# design.net
KiCad netlist of a schematic drawn in Altium Designer
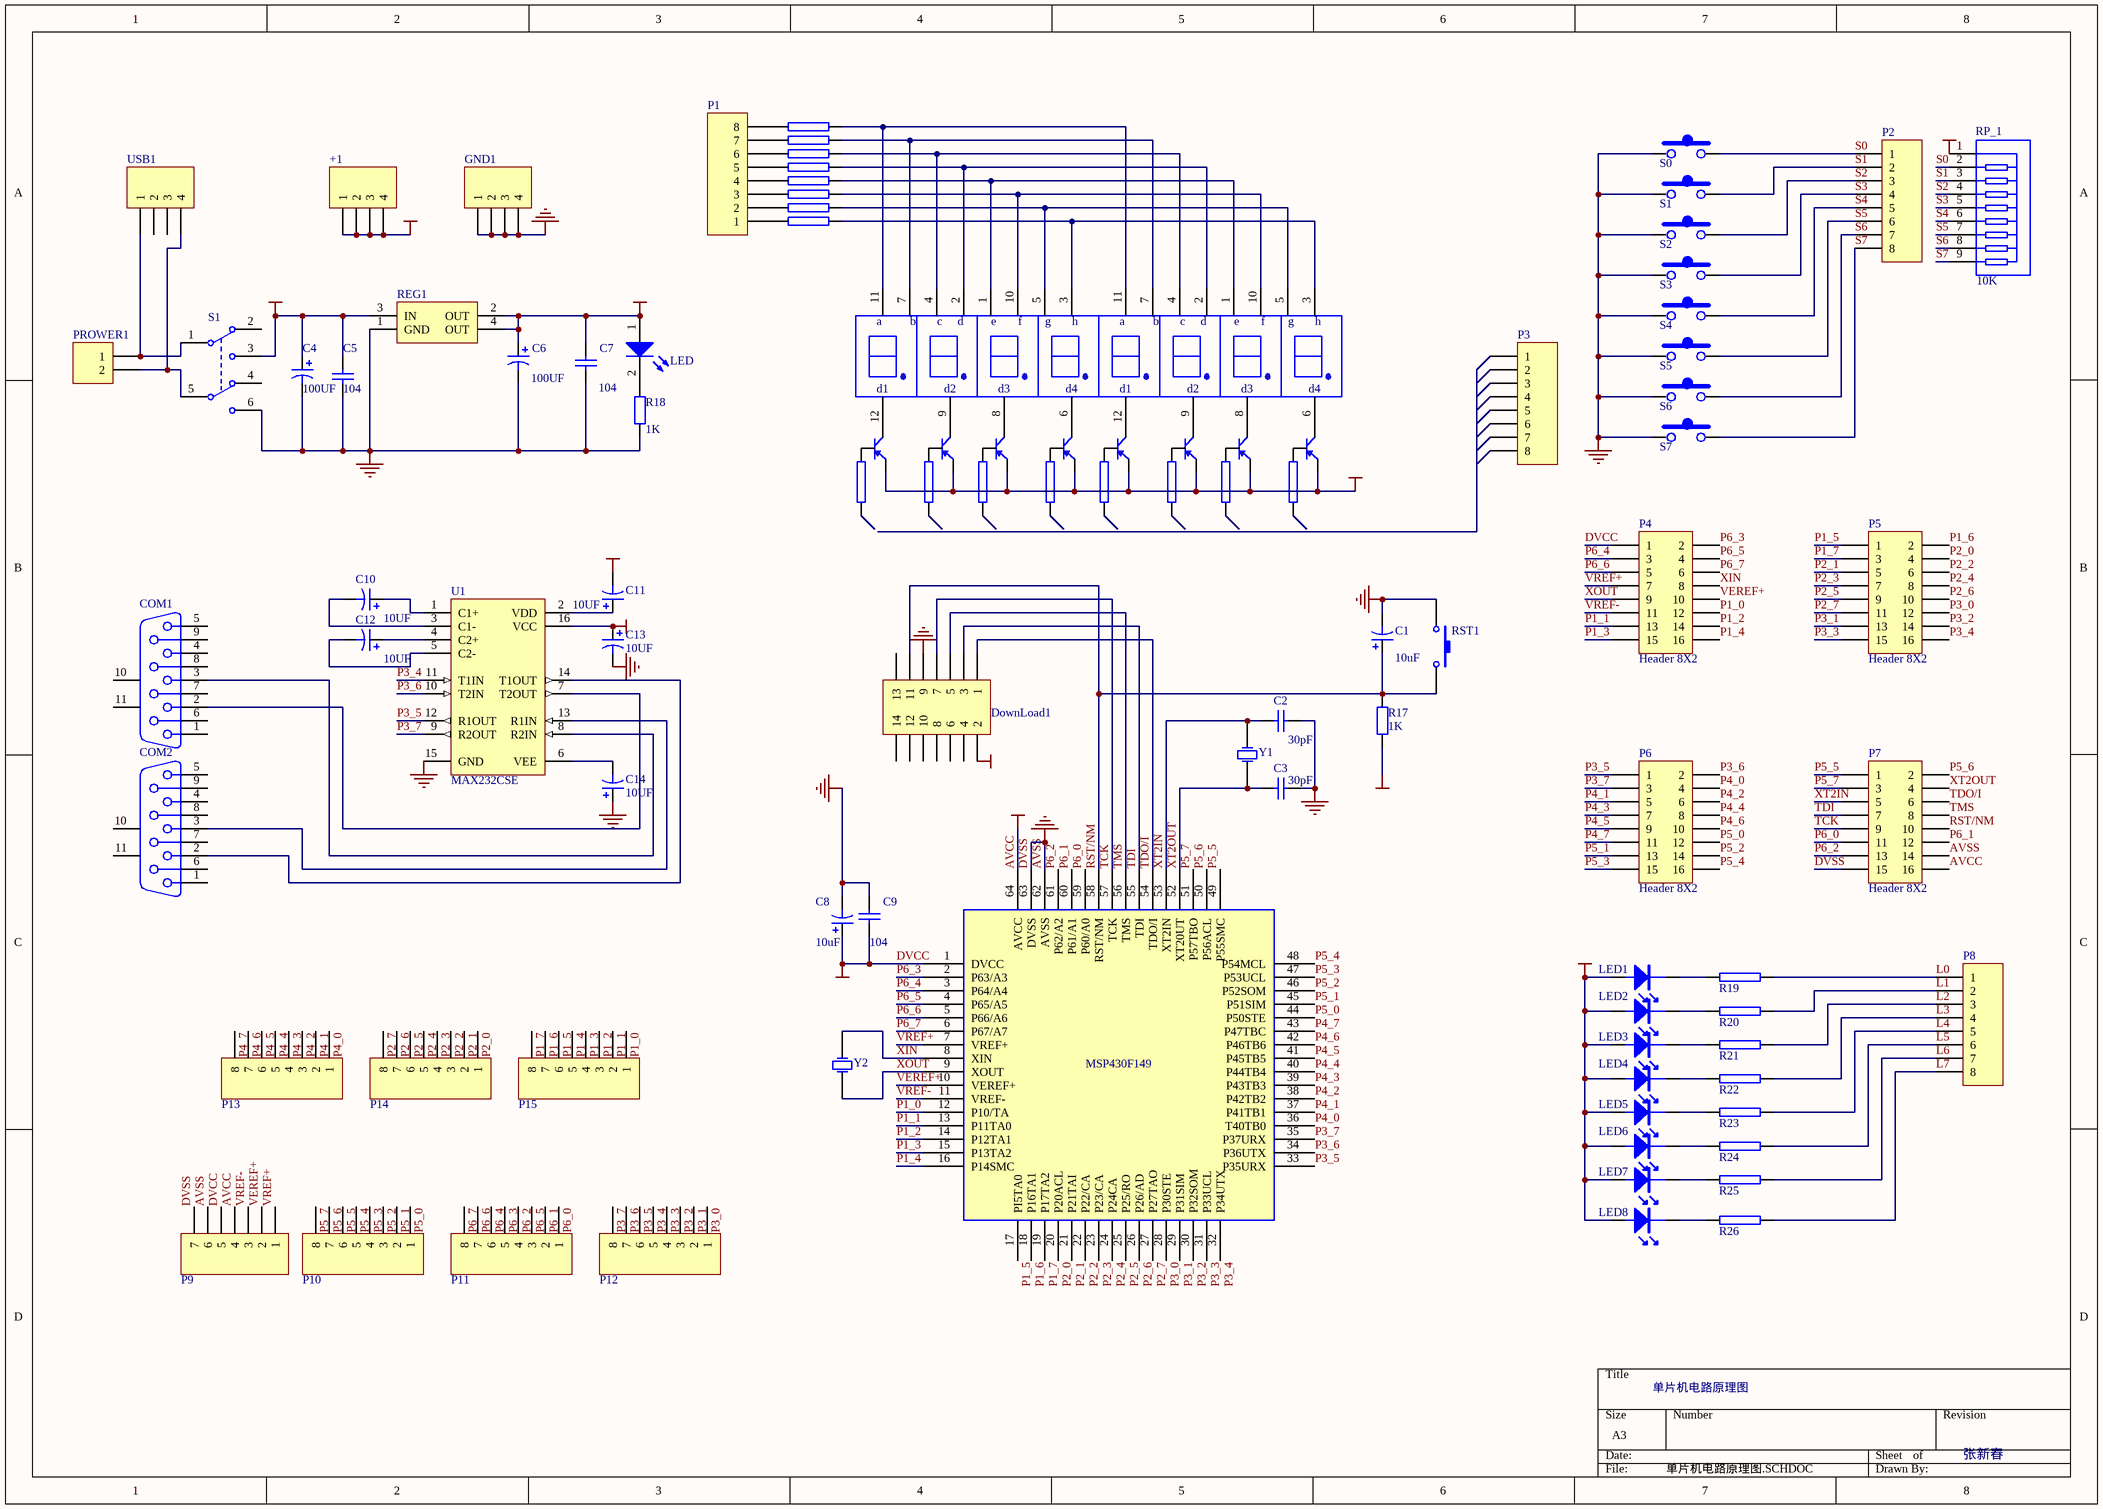
[diagram p0: 单片机电路原理图.SCHDOC]

(export (version "E")
  (design (tool "Eeschema 10.0.6"))
  (components
    (comp (ref "+1")
      (value "Header 4")
      (footprint "HDR1X4")
      (description "Header, 4-Pin")
      (fields (field (name "PUBLISHER") "Altium Limited"))
      (libsource (lib "Miscellaneous Connectors") (part "Header 4"))
    )
    (comp (ref "1") (value "S0") (footprint "an-6*6") (libsource (lib "OldCow1 (1)") (part "KEY")))
    (comp (ref "2") (value "S1") (footprint "an-6*6") (libsource (lib "OldCow1 (1)") (part "KEY")))
    (comp (ref "3") (value "S2") (footprint "an-6*6") (libsource (lib "OldCow1 (1)") (part "KEY")))
    (comp (ref "4") (value "LED8") (footprint "LED8PF") (libsource (lib "OldCow1 (1)") (part "LED8")))
    (comp (ref "5") (value "LED8") (footprint "LED8PF") (libsource (lib "OldCow1 (1)") (part "LED8")))
    (comp (ref "6") (value "S3") (footprint "an-6*6") (libsource (lib "OldCow1 (1)") (part "KEY")))
    (comp (ref "7") (value "S4") (footprint "an-6*6") (libsource (lib "OldCow1 (1)") (part "KEY")))
    (comp (ref "8") (value "S5") (footprint "an-6*6") (libsource (lib "OldCow1 (1)") (part "KEY")))
    (comp (ref "9") (value "NPN1") (footprint "NPN1PF") (libsource (lib "OldCow1 (1)") (part "NPN1")))
    (comp (ref "10") (value "2") (footprint "NPN1PF") (libsource (lib "OldCow1 (1)") (part "NPN1")))
    (comp (ref "11") (value "3") (footprint "NPN1PF") (libsource (lib "OldCow1 (1)") (part "NPN1")))
    (comp (ref "12") (value "NPN1") (footprint "NPN1PF") (libsource (lib "OldCow1 (1)") (part "NPN1")))
    (comp (ref "13") (value "NPN1") (footprint "NPN1PF") (libsource (lib "OldCow1 (1)") (part "NPN1")))
    (comp (ref "14") (value "NPN1") (footprint "NPN1PF") (libsource (lib "OldCow1 (1)") (part "NPN1")))
    (comp (ref "15") (value "NPN1") (footprint "NPN1PF") (libsource (lib "OldCow1 (1)") (part "NPN1")))
    (comp (ref "16") (value "NPN1") (footprint "NPN1PF") (libsource (lib "OldCow1 (1)") (part "NPN1")))
    (comp (ref "17") (value "S6") (footprint "an-6*6") (libsource (lib "OldCow1 (1)") (part "KEY")))
    (comp (ref "18") (value "S7") (footprint "an-6*6") (libsource (lib "OldCow1 (1)") (part "KEY")))
    (comp (ref "C1")
      (value "10uF")
      (footprint "C-DJ-4")
      (description "Polarized Capacitor (Radial)")
      (fields (field (name "Comment") "Cap Pol1") (field (name "PUBLISHER") "Altium Limited"))
      (libsource (lib "Miscellaneous Devices") (part "Cap Pol1"))
    )
    (comp (ref "C2")
      (value "30pF")
      (footprint "CPDR")
      (description "瓷片电容")
      (fields (field (name "Comment") "CPDR") (field (name "PUBLISHER") "Altium Limited"))
      (libsource (lib "zxcourhc") (part "CPDR"))
    )
    (comp (ref "C3")
      (value "30pF")
      (footprint "CPDR")
      (description "瓷片电容")
      (fields (field (name "Comment") "CPDR") (field (name "PUBLISHER") "Altium Limited"))
      (libsource (lib "zxcourhc") (part "CPDR"))
    )
    (comp (ref "C4")
      (value "100UF")
      (footprint "C-DJ-6")
      (description "Polarized Capacitor (Radial)")
      (fields (field (name "Comment") "Cap Pol1") (field (name "PUBLISHER") "Altium Limited"))
      (libsource (lib "Miscellaneous Devices") (part "Cap Pol1"))
    )
    (comp (ref "C5")
      (value "104")
      (footprint "CPDR")
      (description "Capacitor (Semiconductor SIM Model)")
      (fields (field (name "Comment") "Cap Semi") (field (name "PUBLISHER") "Altium Limited"))
      (libsource (lib "Miscellaneous Devices") (part "Cap Semi"))
    )
    (comp (ref "C6")
      (value "100UF")
      (footprint "C-DJ-4")
      (description "Polarized Capacitor (Radial)")
      (fields (field (name "Comment") "Cap Pol1") (field (name "PUBLISHER") "Altium Limited"))
      (libsource (lib "Miscellaneous Devices") (part "Cap Pol1"))
    )
    (comp (ref "C7")
      (value "104")
      (footprint "CPDR")
      (description "Capacitor (Semiconductor SIM Model)")
      (fields (field (name "Comment") "Cap Semi") (field (name "PUBLISHER") "Altium Limited"))
      (libsource (lib "Miscellaneous Devices") (part "Cap Semi"))
    )
    (comp (ref "C8")
      (value "10uF")
      (footprint "C-DJ-4")
      (description "Polarized Capacitor (Radial)")
      (fields (field (name "Comment") "Cap Pol1") (field (name "PUBLISHER") "Altium Limited"))
      (libsource (lib "Miscellaneous Devices") (part "Cap Pol1"))
    )
    (comp (ref "C9")
      (value "104")
      (footprint "CPDR")
      (description "Capacitor (Semiconductor SIM Model)")
      (fields (field (name "Comment") "Cap Semi") (field (name "PUBLISHER") "Altium Limited"))
      (libsource (lib "Miscellaneous Devices") (part "Cap Semi"))
    )
    (comp (ref "C10")
      (value "10UF")
      (footprint "C-DJ-4")
      (description "Polarized Capacitor (Radial)")
      (fields (field (name "Comment") "Cap Pol1") (field (name "PUBLISHER") "Altium Limited"))
      (libsource (lib "Miscellaneous Devices") (part "Cap Pol1"))
    )
    (comp (ref "C11")
      (value "10UF")
      (footprint "C-DJ-4")
      (description "Polarized Capacitor (Radial)")
      (fields (field (name "Comment") "Cap Pol1") (field (name "PUBLISHER") "Altium Limited"))
      (libsource (lib "Miscellaneous Devices") (part "Cap Pol1"))
    )
    (comp (ref "C12")
      (value "10UF")
      (footprint "C-DJ-4")
      (description "Polarized Capacitor (Radial)")
      (fields (field (name "Comment") "Cap Pol1") (field (name "PUBLISHER") "Altium Limited"))
      (libsource (lib "Miscellaneous Devices") (part "Cap Pol1"))
    )
    (comp (ref "C13")
      (value "10UF")
      (footprint "C-DJ-4")
      (description "Polarized Capacitor (Radial)")
      (fields (field (name "Comment") "Cap Pol1") (field (name "PUBLISHER") "Altium Limited"))
      (libsource (lib "Miscellaneous Devices") (part "Cap Pol1"))
    )
    (comp (ref "C14")
      (value "10UF")
      (footprint "C-DJ-4")
      (description "Polarized Capacitor (Radial)")
      (fields (field (name "Comment") "Cap Pol1") (field (name "PUBLISHER") "Altium Limited"))
      (libsource (lib "Miscellaneous Devices") (part "Cap Pol1"))
    )
    (comp (ref "COM1")
      (value "D Connector 9")
      (footprint "zxcourhc:COM-9")
      (description "Receptacle Assembly, 9 Position, Right Angle")
      (fields (field (name "PUBLISHER") "Altium Limited"))
      (libsource (lib "Miscellaneous Connectors") (part "D Connector 9"))
    )
    (comp (ref "COM2")
      (value "D Connector 9")
      (footprint "zxcourhc:COM-9")
      (description "Receptacle Assembly, 9 Position, Right Angle")
      (fields (field (name "PUBLISHER") "Altium Limited"))
      (libsource (lib "Miscellaneous Connectors") (part "D Connector 9"))
    )
    (comp (ref "DownLoad1")
      (value "Header 7X2")
      (footprint "HDR-2X7")
      (description "Header, 7-Pin, Dual row")
      (fields (field (name "PUBLISHER") "Altium Limited"))
      (libsource (lib "Miscellaneous Connectors") (part "Header 7X2"))
    )
    (comp (ref "DS1")
      (value "LED")
      (footprint "LED")
      (description "发光二极管")
      (fields (field (name "PUBLISHER") "Altium Limited"))
      (libsource (lib "zxcourhc") (part "LED"))
    )
    (comp (ref "GND1")
      (value "Header 4")
      (footprint "HDR1X4")
      (description "Header, 4-Pin")
      (fields (field (name "PUBLISHER") "Altium Limited"))
      (libsource (lib "Miscellaneous Connectors") (part "Header 4"))
    )
    (comp (ref "LED1") (value "LED") (footprint "TP-0805-D") (libsource (lib "OldCow1 (1)") (part "LED")))
    (comp (ref "LED2") (value "LED") (footprint "TP-0805-D") (libsource (lib "OldCow1 (1)") (part "LED")))
    (comp (ref "LED3") (value "LED") (footprint "TP-0805-D") (libsource (lib "OldCow1 (1)") (part "LED")))
    (comp (ref "LED4") (value "LED") (footprint "TP-0805-D") (libsource (lib "OldCow1 (1)") (part "LED")))
    (comp (ref "LED5") (value "LED") (footprint "TP-0805-D") (libsource (lib "OldCow1 (1)") (part "LED")))
    (comp (ref "LED6") (value "LED") (footprint "TP-0805-D") (libsource (lib "OldCow1 (1)") (part "LED")))
    (comp (ref "LED7") (value "LED") (footprint "TP-0805-D") (libsource (lib "OldCow1 (1)") (part "LED")))
    (comp (ref "LED8") (value "LED") (footprint "TP-0805-D") (libsource (lib "OldCow1 (1)") (part "LED")))
    (comp (ref "MSP1")
      (value "MSP430F149")
      (footprint "MPS430149")
      (libsource (lib "MyInt_Lib") (part "MSP430F133"))
    )
    (comp (ref "P1")
      (value "Header 8")
      (footprint "HDR1X8")
      (description "Header, 8-Pin")
      (fields (field (name "PUBLISHER") "Altium Limited"))
      (libsource (lib "Miscellaneous Connectors") (part "Header 8"))
    )
    (comp (ref "P2")
      (value "PZ_8")
      (footprint "HDR-8")
      (description "排针——8")
      (fields (field (name "PUBLISHER") "Altium Limited"))
      (libsource (lib "zxcourhc") (part "PZ_8"))
    )
    (comp (ref "P3")
      (value "Header 8")
      (footprint "HDR1X8")
      (description "Header, 8-Pin")
      (fields (field (name "PUBLISHER") "Altium Limited"))
      (libsource (lib "") (part "Header 8_2"))
    )
    (comp (ref "P4")
      (value "Header 8X2")
      (footprint "HDR2X8")
      (description "Header, 8-Pin, Dual row")
      (fields (field (name "PUBLISHER") "Altium Limited"))
      (libsource (lib "Miscellaneous Connectors") (part "Header 8X2"))
    )
    (comp (ref "P5")
      (value "Header 8X2")
      (footprint "HDR2X8")
      (description "Header, 8-Pin, Dual row")
      (fields (field (name "PUBLISHER") "Altium Limited"))
      (libsource (lib "Miscellaneous Connectors") (part "Header 8X2"))
    )
    (comp (ref "P6")
      (value "Header 8X2")
      (footprint "HDR2X8")
      (description "Header, 8-Pin, Dual row")
      (fields (field (name "PUBLISHER") "Altium Limited"))
      (libsource (lib "Miscellaneous Connectors") (part "Header 8X2"))
    )
    (comp (ref "P7")
      (value "Header 8X2")
      (footprint "HDR2X8")
      (description "Header, 8-Pin, Dual row")
      (fields (field (name "PUBLISHER") "Altium Limited"))
      (libsource (lib "Miscellaneous Connectors") (part "Header 8X2"))
    )
    (comp (ref "P8")
      (value "PZ_8")
      (footprint "HDR-8")
      (description "排针——8")
      (fields (field (name "PUBLISHER") "Altium Limited"))
      (libsource (lib "zxcourhc") (part "PZ_8"))
    )
    (comp (ref "P9")
      (value "Header 7")
      (footprint "HDR1X7")
      (description "Header, 7-Pin")
      (fields (field (name "PUBLISHER") "Altium Limited"))
      (libsource (lib "Miscellaneous Connectors") (part "Header 7"))
    )
    (comp (ref "P10")
      (value "Header 8")
      (footprint "zxcourhc:HD-8")
      (description "Header, 8-Pin")
      (fields (field (name "PUBLISHER") "Altium Limited"))
      (libsource (lib "") (part "Header 8_1"))
    )
    (comp (ref "P11")
      (value "Header 8")
      (footprint "zxcourhc:HD-8")
      (description "Header, 8-Pin")
      (fields (field (name "PUBLISHER") "Altium Limited"))
      (libsource (lib "") (part "Header 8_1"))
    )
    (comp (ref "P12")
      (value "Header 8")
      (footprint "zxcourhc:HD-8")
      (description "Header, 8-Pin")
      (fields (field (name "PUBLISHER") "Altium Limited"))
      (libsource (lib "") (part "Header 8_1"))
    )
    (comp (ref "P13")
      (value "Header 8")
      (footprint "zxcourhc:HD-8")
      (description "Header, 8-Pin")
      (fields (field (name "PUBLISHER") "Altium Limited"))
      (libsource (lib "") (part "Header 8_1"))
    )
    (comp (ref "P14")
      (value "Header 8")
      (footprint "zxcourhc:HD-8")
      (description "Header, 8-Pin")
      (fields (field (name "PUBLISHER") "Altium Limited"))
      (libsource (lib "") (part "Header 8_1"))
    )
    (comp (ref "P15")
      (value "Header 8")
      (footprint "zxcourhc:HDR-8")
      (description "Header, 8-Pin")
      (fields (field (name "PUBLISHER") "Altium Limited"))
      (libsource (lib "") (part "Header 8_1"))
    )
    (comp (ref "PROWER1")
      (value "PZ_2")
      (footprint "zxcourhc:JK128_2")
      (description "排针——2")
      (fields (field (name "PUBLISHER") "Altium Limited"))
      (libsource (lib "zxcourhc") (part "PZ_2"))
    )
    (comp (ref "R1") (value "RES1") (footprint "RES1PF") (libsource (lib "") (part "RES1_1")))
    (comp (ref "R2") (value "RES1") (footprint "RES1PF") (libsource (lib "") (part "RES1_1")))
    (comp (ref "R3") (value "RES1") (footprint "RES1PF") (libsource (lib "") (part "RES1_1")))
    (comp (ref "R4") (value "RES1") (footprint "RES1PF") (libsource (lib "") (part "RES1_1")))
    (comp (ref "R5") (value "RES1") (footprint "RES1PF") (libsource (lib "") (part "RES1_1")))
    (comp (ref "R6") (value "RES1") (footprint "RES1PF") (libsource (lib "") (part "RES1_1")))
    (comp (ref "R7") (value "RES1") (footprint "RES1PF") (libsource (lib "") (part "RES1_1")))
    (comp (ref "R8") (value "RES1") (footprint "RES1PF") (libsource (lib "") (part "RES1_1")))
    (comp (ref "R9") (value "RES1") (footprint "RES1PF") (libsource (lib "") (part "RES1_1")))
    (comp (ref "R10") (value "RES1") (footprint "RES1PF") (libsource (lib "") (part "RES1_1")))
    (comp (ref "R11") (value "RES1") (footprint "RES1PF") (libsource (lib "") (part "RES1_1")))
    (comp (ref "R12") (value "RES1") (footprint "RES1PF") (libsource (lib "") (part "RES1_1")))
    (comp (ref "R13") (value "RES1") (footprint "RES1PF") (libsource (lib "") (part "RES1_1")))
    (comp (ref "R14") (value "RES1") (footprint "RES1PF") (libsource (lib "") (part "RES1_1")))
    (comp (ref "R15") (value "RES1") (footprint "RES1PF") (libsource (lib "") (part "RES1_1")))
    (comp (ref "R16") (value "RES1") (footprint "RES1PF") (libsource (lib "") (part "RES1_1")))
    (comp (ref "R17")
      (value "1K")
      (footprint "TP-0805-R")
      (description "电阻")
      (fields (field (name "Comment") "Res") (field (name "PUBLISHER") "Altium Limited"))
      (libsource (lib "zxcourhc") (part "Res"))
    )
    (comp (ref "R18")
      (value "1K")
      (footprint "TP-0805-R")
      (description "电阻")
      (fields (field (name "Comment") "Res") (field (name "PUBLISHER") "Altium Limited"))
      (libsource (lib "zxcourhc") (part "Res"))
    )
    (comp (ref "R19") (value "RES1") (footprint "TP-0805-R") (libsource (lib "OldCow1 (1)") (part "RES1")))
    (comp (ref "R20") (value "RES1") (footprint "TP-0805-R") (libsource (lib "OldCow1 (1)") (part "RES1")))
    (comp (ref "R21") (value "RES1") (footprint "TP-0805-R") (libsource (lib "OldCow1 (1)") (part "RES1")))
    (comp (ref "R22") (value "RES1") (footprint "TP-0805-R") (libsource (lib "OldCow1 (1)") (part "RES1")))
    (comp (ref "R23") (value "RES1") (footprint "TP-0805-R") (libsource (lib "OldCow1 (1)") (part "RES1")))
    (comp (ref "R24") (value "RES1") (footprint "TP-0805-R") (libsource (lib "OldCow1 (1)") (part "RES1")))
    (comp (ref "R25") (value "RES1") (footprint "TP-0805-R") (libsource (lib "OldCow1 (1)") (part "RES1")))
    (comp (ref "R26") (value "RES1") (footprint "TP-0805-R") (libsource (lib "OldCow1 (1)") (part "RES1")))
    (comp (ref "REG1")
      (value "REG1117-3.3")
      (footprint "ZZ311")
      (description "800mA and 1A Low Dropout Positive Regulator 2.85V, 3.3V, 5V, and Adjustable")
      (fields (field (name "PUBLISHER") "Altium Limited"))
      (libsource (lib "BB Power Mgt Voltage Regulator") (part "REG1117-3.3"))
    )
    (comp (ref "RP_1")
      (value "10K")
      (footprint "HDR-10")
      (description "8位排阻")
      (fields (field (name "Comment") "Res PZ_8") (field (name "PUBLISHER") "Altium Limited"))
      (libsource (lib "zxcourhc") (part "Res PZ_8"))
    )
    (comp (ref "RST1")
      (value "AJKG")
      (footprint "an-6*6")
      (description "按键开关")
      (fields (field (name "PUBLISHER") "Altium Limited"))
      (libsource (lib "zxcourhc") (part "AJKG"))
    )
    (comp (ref "S1")
      (value "ZSKG_KEY")
      (footprint "zxcourhc:DPDT-6")
      (description "自锁开关")
      (fields (field (name "PUBLISHER") "Altium Limited"))
      (libsource (lib "zxcourhc") (part "ZSKG_KEY"))
    )
    (comp (ref "U1")
      (value "MAX232CSE")
      (footprint "DIP-16")
      (description "+5V Powered, Multi-Channel RS-232 Driver/Receiver")
      (fields (field (name "PUBLISHER") "Altium Limited"))
      (libsource (lib "Maxim Communication Transceiver") (part "MAX232CSE"))
    )
    (comp (ref "USB1")
      (value "PZ_4")
      (footprint "zxcourhc:USB-5V")
      (description "排针——4")
      (fields (field (name "PUBLISHER") "Altium Limited"))
      (libsource (lib "zxcourhc") (part "PZ_4"))
    )
    (comp (ref "Y1")
      (value "XTAL")
      (footprint "JZ_ZC")
      (description "Crystal Oscillator")
      (fields (field (name "PUBLISHER") "Altium Limited"))
      (libsource (lib "Miscellaneous Devices") (part "XTAL"))
    )
    (comp (ref "Y2")
      (value "XTAL")
      (footprint "BCY-W2/D3.1")
      (description "Crystal Oscillator")
      (fields (field (name "PUBLISHER") "Altium Limited"))
      (libsource (lib "Miscellaneous Devices") (part "XTAL"))
    )
  )
  (nets
    (net (code "1") (name "+5V") (class "Default")
      (node (ref "+1") (pin "1") (pinfunction "1_1") (pintype "passive"))
      (node (ref "+1") (pin "2") (pinfunction "2_2") (pintype "passive"))
      (node (ref "+1") (pin "3") (pinfunction "3_3") (pintype "passive"))
      (node (ref "+1") (pin "4") (pinfunction "4_4") (pintype "passive"))
      (node (ref "C11") (pin "2") (pinfunction "2_2") (pintype "passive"))
      (node (ref "C13") (pin "1") (pinfunction "1_1") (pintype "passive"))
      (node (ref "C4") (pin "1") (pinfunction "1_1") (pintype "passive"))
      (node (ref "C5") (pin "2") (pinfunction "2_2") (pintype "passive"))
      (node (ref "REG1") (pin "3") (pinfunction "IN_3") (pintype "power_in"))
      (node (ref "S1") (pin "3") (pinfunction "NO1_3") (pintype "passive"))
      (node (ref "U1") (pin "16") (pinfunction "VCC_16") (pintype "power_in"))
    )
    (net (code "2") (name "/L0") (class "Default")
      (node (ref "P8") (pin "1") (pinfunction "1_1") (pintype "passive"))
      (node (ref "R19") (pin "1") (pinfunction "1_1") (pintype "passive"))
    )
    (net (code "3") (name "/L1") (class "Default")
      (node (ref "P8") (pin "2") (pinfunction "2_2") (pintype "passive"))
      (node (ref "R20") (pin "1") (pinfunction "1_1") (pintype "passive"))
    )
    (net (code "4") (name "/L2") (class "Default")
      (node (ref "P8") (pin "3") (pinfunction "3_3") (pintype "passive"))
      (node (ref "R21") (pin "1") (pinfunction "1_1") (pintype "passive"))
    )
    (net (code "5") (name "/L3") (class "Default")
      (node (ref "P8") (pin "4") (pinfunction "4_4") (pintype "passive"))
      (node (ref "R22") (pin "1") (pinfunction "1_1") (pintype "passive"))
    )
    (net (code "6") (name "/L4") (class "Default")
      (node (ref "P8") (pin "5") (pinfunction "5_5") (pintype "passive"))
      (node (ref "R23") (pin "1") (pinfunction "1_1") (pintype "passive"))
    )
    (net (code "7") (name "/L5") (class "Default")
      (node (ref "P8") (pin "6") (pinfunction "6_6") (pintype "passive"))
      (node (ref "R24") (pin "1") (pinfunction "1_1") (pintype "passive"))
    )
    (net (code "8") (name "/L6") (class "Default")
      (node (ref "P8") (pin "7") (pinfunction "7_7") (pintype "passive"))
      (node (ref "R25") (pin "1") (pinfunction "1_1") (pintype "passive"))
    )
    (net (code "9") (name "/L7") (class "Default")
      (node (ref "P8") (pin "8") (pinfunction "8_8") (pintype "passive"))
      (node (ref "R26") (pin "1") (pinfunction "1_1") (pintype "passive"))
    )
    (net (code "10") (name "/P1_0") (class "Default")
      (node (ref "MSP1") (pin "12") (pinfunction "P10/TA_12") (pintype "passive"))
      (node (ref "P15") (pin "1") (pinfunction "1_1") (pintype "passive"))
      (node (ref "P4") (pin "12") (pinfunction "12_12") (pintype "passive"))
    )
    (net (code "11") (name "/P1_1") (class "Default")
      (node (ref "MSP1") (pin "13") (pinfunction "P11TA0_13") (pintype "passive"))
      (node (ref "P15") (pin "2") (pinfunction "2_2") (pintype "passive"))
      (node (ref "P4") (pin "13") (pinfunction "13_13") (pintype "passive"))
    )
    (net (code "12") (name "/P1_2") (class "Default")
      (node (ref "MSP1") (pin "14") (pinfunction "P12TA1_14") (pintype "passive"))
      (node (ref "P15") (pin "3") (pinfunction "3_3") (pintype "passive"))
      (node (ref "P4") (pin "14") (pinfunction "14_14") (pintype "passive"))
    )
    (net (code "13") (name "/P1_3") (class "Default")
      (node (ref "MSP1") (pin "15") (pinfunction "P13TA2_15") (pintype "passive"))
      (node (ref "P15") (pin "4") (pinfunction "4_4") (pintype "passive"))
      (node (ref "P4") (pin "15") (pinfunction "15_15") (pintype "passive"))
    )
    (net (code "14") (name "/P1_4") (class "Default")
      (node (ref "MSP1") (pin "16") (pinfunction "P14SMC_16") (pintype "passive"))
      (node (ref "P15") (pin "5") (pinfunction "5_5") (pintype "passive"))
      (node (ref "P4") (pin "16") (pinfunction "16_16") (pintype "passive"))
    )
    (net (code "15") (name "/P1_5") (class "Default")
      (node (ref "MSP1") (pin "17") (pinfunction "PI5TA0_17") (pintype "passive"))
      (node (ref "P15") (pin "6") (pinfunction "6_6") (pintype "passive"))
      (node (ref "P5") (pin "1") (pinfunction "1_1") (pintype "passive"))
    )
    (net (code "16") (name "/P1_6") (class "Default")
      (node (ref "MSP1") (pin "18") (pinfunction "P16TA1_18") (pintype "passive"))
      (node (ref "P15") (pin "7") (pinfunction "7_7") (pintype "passive"))
      (node (ref "P5") (pin "2") (pinfunction "2_2") (pintype "passive"))
    )
    (net (code "17") (name "/P1_7") (class "Default")
      (node (ref "MSP1") (pin "19") (pinfunction "P17TA2_19") (pintype "passive"))
      (node (ref "P15") (pin "8") (pinfunction "8_8") (pintype "passive"))
      (node (ref "P5") (pin "3") (pinfunction "3_3") (pintype "passive"))
    )
    (net (code "18") (name "/P2_0") (class "Default")
      (node (ref "MSP1") (pin "20") (pinfunction "P20ACL_20") (pintype "passive"))
      (node (ref "P14") (pin "1") (pinfunction "1_1") (pintype "passive"))
      (node (ref "P5") (pin "4") (pinfunction "4_4") (pintype "passive"))
    )
    (net (code "19") (name "/P2_1") (class "Default")
      (node (ref "MSP1") (pin "21") (pinfunction "P21TAI_21") (pintype "passive"))
      (node (ref "P14") (pin "2") (pinfunction "2_2") (pintype "passive"))
      (node (ref "P5") (pin "5") (pinfunction "5_5") (pintype "passive"))
    )
    (net (code "20") (name "/P2_2") (class "Default")
      (node (ref "MSP1") (pin "22") (pinfunction "P22/CA_22") (pintype "passive"))
      (node (ref "P14") (pin "3") (pinfunction "3_3") (pintype "passive"))
      (node (ref "P5") (pin "6") (pinfunction "6_6") (pintype "passive"))
    )
    (net (code "21") (name "/P2_3") (class "Default")
      (node (ref "MSP1") (pin "23") (pinfunction "P23/CA_23") (pintype "passive"))
      (node (ref "P14") (pin "4") (pinfunction "4_4") (pintype "passive"))
      (node (ref "P5") (pin "7") (pinfunction "7_7") (pintype "passive"))
    )
    (net (code "22") (name "/P2_4") (class "Default")
      (node (ref "MSP1") (pin "24") (pinfunction "P24CA_24") (pintype "passive"))
      (node (ref "P14") (pin "5") (pinfunction "5_5") (pintype "passive"))
      (node (ref "P5") (pin "8") (pinfunction "8_8") (pintype "passive"))
    )
    (net (code "23") (name "/P2_5") (class "Default")
      (node (ref "MSP1") (pin "25") (pinfunction "P25/RO_25") (pintype "passive"))
      (node (ref "P14") (pin "6") (pinfunction "6_6") (pintype "passive"))
      (node (ref "P5") (pin "9") (pinfunction "9_9") (pintype "passive"))
    )
    (net (code "24") (name "/P2_6") (class "Default")
      (node (ref "MSP1") (pin "26") (pinfunction "P26/AD_26") (pintype "passive"))
      (node (ref "P14") (pin "7") (pinfunction "7_7") (pintype "passive"))
      (node (ref "P5") (pin "10") (pinfunction "10_10") (pintype "passive"))
    )
    (net (code "25") (name "/P2_7") (class "Default")
      (node (ref "MSP1") (pin "27") (pinfunction "P27TAO_27") (pintype "passive"))
      (node (ref "P14") (pin "8") (pinfunction "8_8") (pintype "passive"))
      (node (ref "P5") (pin "11") (pinfunction "11_11") (pintype "passive"))
    )
    (net (code "26") (name "/P3_0") (class "Default")
      (node (ref "MSP1") (pin "28") (pinfunction "P30STE_28") (pintype "passive"))
      (node (ref "P12") (pin "1") (pinfunction "1_1") (pintype "passive"))
      (node (ref "P5") (pin "12") (pinfunction "12_12") (pintype "passive"))
    )
    (net (code "27") (name "/P3_1") (class "Default")
      (node (ref "MSP1") (pin "29") (pinfunction "P31SIM_29") (pintype "passive"))
      (node (ref "P12") (pin "2") (pinfunction "2_2") (pintype "passive"))
      (node (ref "P5") (pin "13") (pinfunction "13_13") (pintype "passive"))
    )
    (net (code "28") (name "/P3_2") (class "Default")
      (node (ref "MSP1") (pin "30") (pinfunction "P32SOM_30") (pintype "passive"))
      (node (ref "P12") (pin "3") (pinfunction "3_3") (pintype "passive"))
      (node (ref "P5") (pin "14") (pinfunction "14_14") (pintype "passive"))
    )
    (net (code "29") (name "/P3_3") (class "Default")
      (node (ref "MSP1") (pin "31") (pinfunction "P33UCL_31") (pintype "passive"))
      (node (ref "P12") (pin "4") (pinfunction "4_4") (pintype "passive"))
      (node (ref "P5") (pin "15") (pinfunction "15_15") (pintype "passive"))
    )
    (net (code "30") (name "/P3_4") (class "Default")
      (node (ref "MSP1") (pin "32") (pinfunction "P34UTX_32") (pintype "passive"))
      (node (ref "P12") (pin "5") (pinfunction "5_5") (pintype "passive"))
      (node (ref "P5") (pin "16") (pinfunction "16_16") (pintype "passive"))
      (node (ref "U1") (pin "11") (pinfunction "T1IN_11") (pintype "input"))
    )
    (net (code "31") (name "/P3_5") (class "Default")
      (node (ref "MSP1") (pin "33") (pinfunction "P35URX_33") (pintype "passive"))
      (node (ref "P12") (pin "6") (pinfunction "6_6") (pintype "passive"))
      (node (ref "P6") (pin "1") (pinfunction "1_1") (pintype "passive"))
      (node (ref "U1") (pin "12") (pinfunction "R1OUT_12") (pintype "output"))
    )
    (net (code "32") (name "/P3_6") (class "Default")
      (node (ref "MSP1") (pin "34") (pinfunction "P36UTX_34") (pintype "passive"))
      (node (ref "P12") (pin "7") (pinfunction "7_7") (pintype "passive"))
      (node (ref "P6") (pin "2") (pinfunction "2_2") (pintype "passive"))
      (node (ref "U1") (pin "10") (pinfunction "T2IN_10") (pintype "input"))
    )
    (net (code "33") (name "/P3_7") (class "Default")
      (node (ref "MSP1") (pin "35") (pinfunction "P37URX_35") (pintype "passive"))
      (node (ref "P12") (pin "8") (pinfunction "8_8") (pintype "passive"))
      (node (ref "P6") (pin "3") (pinfunction "3_3") (pintype "passive"))
      (node (ref "U1") (pin "9") (pinfunction "R2OUT_9") (pintype "output"))
    )
    (net (code "34") (name "/P4_0") (class "Default")
      (node (ref "MSP1") (pin "36") (pinfunction "T40TB0_36") (pintype "passive"))
      (node (ref "P13") (pin "1") (pinfunction "1_1") (pintype "passive"))
      (node (ref "P6") (pin "4") (pinfunction "4_4") (pintype "passive"))
    )
    (net (code "35") (name "/P4_1") (class "Default")
      (node (ref "MSP1") (pin "37") (pinfunction "P41TB1_37") (pintype "passive"))
      (node (ref "P13") (pin "2") (pinfunction "2_2") (pintype "passive"))
      (node (ref "P6") (pin "5") (pinfunction "5_5") (pintype "passive"))
    )
    (net (code "36") (name "/P4_2") (class "Default")
      (node (ref "MSP1") (pin "38") (pinfunction "P42TB2_38") (pintype "passive"))
      (node (ref "P13") (pin "3") (pinfunction "3_3") (pintype "passive"))
      (node (ref "P6") (pin "6") (pinfunction "6_6") (pintype "passive"))
    )
    (net (code "37") (name "/P4_3") (class "Default")
      (node (ref "MSP1") (pin "39") (pinfunction "P43TB3_39") (pintype "passive"))
      (node (ref "P13") (pin "4") (pinfunction "4_4") (pintype "passive"))
      (node (ref "P6") (pin "7") (pinfunction "7_7") (pintype "passive"))
    )
    (net (code "38") (name "/P4_4") (class "Default")
      (node (ref "MSP1") (pin "40") (pinfunction "P44TB4_40") (pintype "passive"))
      (node (ref "P13") (pin "5") (pinfunction "5_5") (pintype "passive"))
      (node (ref "P6") (pin "8") (pinfunction "8_8") (pintype "passive"))
    )
    (net (code "39") (name "/P4_5") (class "Default")
      (node (ref "MSP1") (pin "41") (pinfunction "P45TB5_41") (pintype "passive"))
      (node (ref "P13") (pin "6") (pinfunction "6_6") (pintype "passive"))
      (node (ref "P6") (pin "9") (pinfunction "9_9") (pintype "passive"))
    )
    (net (code "40") (name "/P4_6") (class "Default")
      (node (ref "MSP1") (pin "42") (pinfunction "P46TB6_42") (pintype "passive"))
      (node (ref "P13") (pin "7") (pinfunction "7_7") (pintype "passive"))
      (node (ref "P6") (pin "10") (pinfunction "10_10") (pintype "passive"))
    )
    (net (code "41") (name "/P4_7") (class "Default")
      (node (ref "MSP1") (pin "43") (pinfunction "P47TBC_43") (pintype "passive"))
      (node (ref "P13") (pin "8") (pinfunction "8_8") (pintype "passive"))
      (node (ref "P6") (pin "11") (pinfunction "11_11") (pintype "passive"))
    )
    (net (code "42") (name "/P5_0") (class "Default")
      (node (ref "MSP1") (pin "44") (pinfunction "P50STE_44") (pintype "passive"))
      (node (ref "P10") (pin "1") (pinfunction "1_1") (pintype "passive"))
      (node (ref "P6") (pin "12") (pinfunction "12_12") (pintype "passive"))
    )
    (net (code "43") (name "/P5_1") (class "Default")
      (node (ref "MSP1") (pin "45") (pinfunction "P51SIM_45") (pintype "passive"))
      (node (ref "P10") (pin "2") (pinfunction "2_2") (pintype "passive"))
      (node (ref "P6") (pin "13") (pinfunction "13_13") (pintype "passive"))
    )
    (net (code "44") (name "/P5_2") (class "Default")
      (node (ref "MSP1") (pin "46") (pinfunction "P52SOM_46") (pintype "passive"))
      (node (ref "P10") (pin "3") (pinfunction "3_3") (pintype "passive"))
      (node (ref "P6") (pin "14") (pinfunction "14_14") (pintype "passive"))
    )
    (net (code "45") (name "/P5_3") (class "Default")
      (node (ref "MSP1") (pin "47") (pinfunction "P53UCL_47") (pintype "passive"))
      (node (ref "P10") (pin "4") (pinfunction "4_4") (pintype "passive"))
      (node (ref "P6") (pin "15") (pinfunction "15_15") (pintype "passive"))
    )
    (net (code "46") (name "/P5_4") (class "Default")
      (node (ref "MSP1") (pin "48") (pinfunction "P54MCL_48") (pintype "passive"))
      (node (ref "P10") (pin "5") (pinfunction "5_5") (pintype "passive"))
      (node (ref "P6") (pin "16") (pinfunction "16_16") (pintype "passive"))
    )
    (net (code "47") (name "/P5_5") (class "Default")
      (node (ref "MSP1") (pin "49") (pinfunction "P55SMC_49") (pintype "passive"))
      (node (ref "P10") (pin "6") (pinfunction "6_6") (pintype "passive"))
      (node (ref "P7") (pin "1") (pinfunction "1_1") (pintype "passive"))
    )
    (net (code "48") (name "/P5_6") (class "Default")
      (node (ref "MSP1") (pin "50") (pinfunction "P56ACL_50") (pintype "passive"))
      (node (ref "P10") (pin "7") (pinfunction "7_7") (pintype "passive"))
      (node (ref "P7") (pin "2") (pinfunction "2_2") (pintype "passive"))
    )
    (net (code "49") (name "/P5_7") (class "Default")
      (node (ref "MSP1") (pin "51") (pinfunction "P57TBO_51") (pintype "passive"))
      (node (ref "P10") (pin "8") (pinfunction "8_8") (pintype "passive"))
      (node (ref "P7") (pin "3") (pinfunction "3_3") (pintype "passive"))
    )
    (net (code "50") (name "/P6_0") (class "Default")
      (node (ref "MSP1") (pin "59") (pinfunction "P60/A0_59") (pintype "passive"))
      (node (ref "P11") (pin "1") (pinfunction "1_1") (pintype "passive"))
      (node (ref "P7") (pin "11") (pinfunction "11_11") (pintype "passive"))
    )
    (net (code "51") (name "/P6_1") (class "Default")
      (node (ref "MSP1") (pin "60") (pinfunction "P61/A1_60") (pintype "passive"))
      (node (ref "P11") (pin "2") (pinfunction "2_2") (pintype "passive"))
      (node (ref "P7") (pin "12") (pinfunction "12_12") (pintype "passive"))
    )
    (net (code "52") (name "/P6_2") (class "Default")
      (node (ref "MSP1") (pin "61") (pinfunction "P62/A2_61") (pintype "passive"))
      (node (ref "P11") (pin "4") (pinfunction "4_4") (pintype "passive"))
      (node (ref "P7") (pin "13") (pinfunction "13_13") (pintype "passive"))
    )
    (net (code "53") (name "/P6_3") (class "Default")
      (node (ref "MSP1") (pin "2") (pinfunction "P63/A3_2") (pintype "passive"))
      (node (ref "P11") (pin "5") (pinfunction "5_5") (pintype "passive"))
      (node (ref "P4") (pin "2") (pinfunction "2_2") (pintype "passive"))
    )
    (net (code "54") (name "/P6_4") (class "Default")
      (node (ref "MSP1") (pin "3") (pinfunction "P64/A4_3") (pintype "passive"))
      (node (ref "P11") (pin "6") (pinfunction "6_6") (pintype "passive"))
      (node (ref "P4") (pin "3") (pinfunction "3_3") (pintype "passive"))
    )
    (net (code "55") (name "/P6_5") (class "Default")
      (node (ref "MSP1") (pin "4") (pinfunction "P65/A5_4") (pintype "passive"))
      (node (ref "P11") (pin "3") (pinfunction "3_3") (pintype "passive"))
      (node (ref "P4") (pin "4") (pinfunction "4_4") (pintype "passive"))
    )
    (net (code "56") (name "/P6_6") (class "Default")
      (node (ref "MSP1") (pin "5") (pinfunction "P66/A6_5") (pintype "passive"))
      (node (ref "P11") (pin "7") (pinfunction "7_7") (pintype "passive"))
      (node (ref "P4") (pin "5") (pinfunction "5_5") (pintype "passive"))
    )
    (net (code "57") (name "/P6_7") (class "Default")
      (node (ref "MSP1") (pin "6") (pinfunction "P67/A7_6") (pintype "passive"))
      (node (ref "P11") (pin "8") (pinfunction "8_8") (pintype "passive"))
      (node (ref "P4") (pin "6") (pinfunction "6_6") (pintype "passive"))
    )
    (net (code "58") (name "/RST{slash}NM") (class "Default")
      (node (ref "C1") (pin "1") (pinfunction "1_1") (pintype "passive"))
      (node (ref "DownLoad1") (pin "11") (pinfunction "11_11") (pintype "passive"))
      (node (ref "MSP1") (pin "58") (pinfunction "RST/NM_58") (pintype "passive"))
      (node (ref "P7") (pin "10") (pinfunction "10_10") (pintype "passive"))
      (node (ref "R17") (pin "2") (pinfunction "2_2") (pintype "passive"))
      (node (ref "RST1") (pin "2") (pinfunction "2_2") (pintype "passive"))
    )
    (net (code "59") (name "/S0") (class "Default")
      (node (ref "1") (pin "2") (pinfunction "2_2") (pintype "passive"))
      (node (ref "P2") (pin "1") (pinfunction "1_1") (pintype "passive"))
      (node (ref "RP_1") (pin "2") (pinfunction "2_2") (pintype "passive"))
    )
    (net (code "60") (name "/S1") (class "Default")
      (node (ref "2") (pin "2") (pinfunction "2_2") (pintype "passive"))
      (node (ref "P2") (pin "2") (pinfunction "2_2") (pintype "passive"))
      (node (ref "RP_1") (pin "3") (pinfunction "3_3") (pintype "passive"))
    )
    (net (code "61") (name "/S2") (class "Default")
      (node (ref "3") (pin "2") (pinfunction "2_2") (pintype "passive"))
      (node (ref "P2") (pin "3") (pinfunction "3_3") (pintype "passive"))
      (node (ref "RP_1") (pin "4") (pinfunction "4_4") (pintype "passive"))
    )
    (net (code "62") (name "/S3") (class "Default")
      (node (ref "6") (pin "2") (pinfunction "2_2") (pintype "passive"))
      (node (ref "P2") (pin "4") (pinfunction "4_4") (pintype "passive"))
      (node (ref "RP_1") (pin "5") (pinfunction "5_5") (pintype "passive"))
    )
    (net (code "63") (name "/S4") (class "Default")
      (node (ref "7") (pin "2") (pinfunction "2_2") (pintype "passive"))
      (node (ref "P2") (pin "5") (pinfunction "5_5") (pintype "passive"))
      (node (ref "RP_1") (pin "6") (pinfunction "6_6") (pintype "passive"))
    )
    (net (code "64") (name "/S5") (class "Default")
      (node (ref "8") (pin "2") (pinfunction "2_2") (pintype "passive"))
      (node (ref "P2") (pin "6") (pinfunction "6_6") (pintype "passive"))
      (node (ref "RP_1") (pin "7") (pinfunction "7_7") (pintype "passive"))
    )
    (net (code "65") (name "/S6") (class "Default")
      (node (ref "17") (pin "2") (pinfunction "2_2") (pintype "passive"))
      (node (ref "P2") (pin "7") (pinfunction "7_7") (pintype "passive"))
      (node (ref "RP_1") (pin "8") (pinfunction "8_8") (pintype "passive"))
    )
    (net (code "66") (name "/S7") (class "Default")
      (node (ref "18") (pin "2") (pinfunction "2_2") (pintype "passive"))
      (node (ref "P2") (pin "8") (pinfunction "8_8") (pintype "passive"))
      (node (ref "RP_1") (pin "9") (pinfunction "9_9") (pintype "passive"))
    )
    (net (code "67") (name "/TCK") (class "Default")
      (node (ref "DownLoad1") (pin "7") (pinfunction "7_7") (pintype "passive"))
      (node (ref "MSP1") (pin "57") (pinfunction "TCK_57") (pintype "passive"))
      (node (ref "P7") (pin "9") (pinfunction "9_9") (pintype "passive"))
    )
    (net (code "68") (name "/TDI") (class "Default")
      (node (ref "DownLoad1") (pin "3") (pinfunction "3_3") (pintype "passive"))
      (node (ref "MSP1") (pin "55") (pinfunction "TDI_55") (pintype "passive"))
      (node (ref "P7") (pin "7") (pinfunction "7_7") (pintype "passive"))
    )
    (net (code "69") (name "/TDO{slash}I") (class "Default")
      (node (ref "DownLoad1") (pin "1") (pinfunction "1_1") (pintype "passive"))
      (node (ref "MSP1") (pin "54") (pinfunction "TDO/I_54") (pintype "passive"))
      (node (ref "P7") (pin "6") (pinfunction "6_6") (pintype "passive"))
    )
    (net (code "70") (name "/TMS") (class "Default")
      (node (ref "DownLoad1") (pin "5") (pinfunction "5_5") (pintype "passive"))
      (node (ref "MSP1") (pin "56") (pinfunction "TMS_56") (pintype "passive"))
      (node (ref "P7") (pin "8") (pinfunction "8_8") (pintype "passive"))
    )
    (net (code "71") (name "/VEREF+") (class "Default")
      (node (ref "MSP1") (pin "10") (pinfunction "VEREF+_10") (pintype "passive"))
      (node (ref "P4") (pin "10") (pinfunction "10_10") (pintype "passive"))
      (node (ref "P9") (pin "2") (pinfunction "2_2") (pintype "passive"))
    )
    (net (code "72") (name "/VREF+") (class "Default")
      (node (ref "MSP1") (pin "7") (pinfunction "VREF+_7") (pintype "passive"))
      (node (ref "P4") (pin "7") (pinfunction "7_7") (pintype "passive"))
      (node (ref "P9") (pin "1") (pinfunction "1_1") (pintype "passive"))
    )
    (net (code "73") (name "/VREF-") (class "Default")
      (node (ref "MSP1") (pin "11") (pinfunction "VREF-_11") (pintype "passive"))
      (node (ref "P4") (pin "11") (pinfunction "11_11") (pintype "passive"))
      (node (ref "P9") (pin "3") (pinfunction "3_3") (pintype "passive"))
    )
    (net (code "74") (name "/XIN") (class "Default")
      (node (ref "MSP1") (pin "8") (pinfunction "XIN_8") (pintype "passive"))
      (node (ref "P4") (pin "8") (pinfunction "8_8") (pintype "passive"))
      (node (ref "Y2") (pin "1") (pinfunction "OSC1_1") (pintype "passive"))
    )
    (net (code "75") (name "/XOUT") (class "Default")
      (node (ref "MSP1") (pin "9") (pinfunction "XOUT_9") (pintype "passive"))
      (node (ref "P4") (pin "9") (pinfunction "9_9") (pintype "passive"))
      (node (ref "Y2") (pin "2") (pinfunction "OSC2_2") (pintype "passive"))
    )
    (net (code "76") (name "/XT2IN") (class "Default")
      (node (ref "C2") (pin "1") (pinfunction "1_1") (pintype "passive"))
      (node (ref "MSP1") (pin "53") (pinfunction "XT2IN_53") (pintype "passive"))
      (node (ref "P7") (pin "5") (pinfunction "5_5") (pintype "passive"))
      (node (ref "Y1") (pin "2") (pinfunction "OSC2_2") (pintype "passive"))
    )
    (net (code "77") (name "/XT2OUT") (class "Default")
      (node (ref "C3") (pin "1") (pinfunction "1_1") (pintype "passive"))
      (node (ref "MSP1") (pin "52") (pinfunction "XT20UT_52") (pintype "passive"))
      (node (ref "P7") (pin "4") (pinfunction "4_4") (pintype "passive"))
      (node (ref "Y1") (pin "1") (pinfunction "OSC1_1") (pintype "passive"))
    )
    (net (code "78") (name "GND") (class "Default")
      (node (ref "1") (pin "1") (pinfunction "1_1") (pintype "passive"))
      (node (ref "17") (pin "1") (pinfunction "1_1") (pintype "passive"))
      (node (ref "18") (pin "1") (pinfunction "1_1") (pintype "passive"))
      (node (ref "2") (pin "1") (pinfunction "1_1") (pintype "passive"))
      (node (ref "3") (pin "1") (pinfunction "1_1") (pintype "passive"))
      (node (ref "6") (pin "1") (pinfunction "1_1") (pintype "passive"))
      (node (ref "7") (pin "1") (pinfunction "1_1") (pintype "passive"))
      (node (ref "8") (pin "1") (pinfunction "1_1") (pintype "passive"))
      (node (ref "C1") (pin "2") (pinfunction "2_2") (pintype "passive"))
      (node (ref "C13") (pin "2") (pinfunction "2_2") (pintype "passive"))
      (node (ref "C14") (pin "1") (pinfunction "1_1") (pintype "passive"))
      (node (ref "C2") (pin "2") (pinfunction "2_2") (pintype "passive"))
      (node (ref "C3") (pin "2") (pinfunction "2_2") (pintype "passive"))
      (node (ref "C4") (pin "2") (pinfunction "2_2") (pintype "passive"))
      (node (ref "C5") (pin "1") (pinfunction "1_1") (pintype "passive"))
      (node (ref "C6") (pin "2") (pinfunction "2_2") (pintype "passive"))
      (node (ref "C7") (pin "1") (pinfunction "1_1") (pintype "passive"))
      (node (ref "C8") (pin "2") (pinfunction "2_2") (pintype "passive"))
      (node (ref "C9") (pin "2") (pinfunction "2_2") (pintype "passive"))
      (node (ref "DownLoad1") (pin "9") (pinfunction "9_9") (pintype "passive"))
      (node (ref "GND1") (pin "1") (pinfunction "1_1") (pintype "passive"))
      (node (ref "GND1") (pin "2") (pinfunction "2_2") (pintype "passive"))
      (node (ref "GND1") (pin "3") (pinfunction "3_3") (pintype "passive"))
      (node (ref "GND1") (pin "4") (pinfunction "4_4") (pintype "passive"))
      (node (ref "MSP1") (pin "62") (pinfunction "AVSS_62") (pintype "passive"))
      (node (ref "MSP1") (pin "63") (pinfunction "DVSS_63") (pintype "passive"))
      (node (ref "P7") (pin "14") (pinfunction "14_14") (pintype "passive"))
      (node (ref "P7") (pin "15") (pinfunction "15_15") (pintype "passive"))
      (node (ref "P9") (pin "6") (pinfunction "6_6") (pintype "passive"))
      (node (ref "P9") (pin "7") (pinfunction "7_7") (pintype "passive"))
      (node (ref "R18") (pin "1") (pinfunction "1_1") (pintype "passive"))
      (node (ref "REG1") (pin "1") (pinfunction "GND_1") (pintype "power_in"))
      (node (ref "RST1") (pin "1") (pinfunction "1_1") (pintype "passive"))
      (node (ref "S1") (pin "6") (pinfunction "NO2_6") (pintype "passive"))
      (node (ref "U1") (pin "15") (pinfunction "GND_15") (pintype "power_in"))
    )
    (net (code "79") (name "Net-(4-Pad1)") (class "Default")
      (node (ref "4") (pin "1") (pinfunction "1_1") (pintype "passive"))
      (node (ref "5") (pin "1") (pinfunction "1_1") (pintype "passive"))
      (node (ref "R5") (pin "2") (pinfunction "2_2") (pintype "passive"))
    )
    (net (code "80") (name "Net-(4-Pad2)") (class "Default")
      (node (ref "4") (pin "2") (pinfunction "2_2") (pintype "passive"))
      (node (ref "5") (pin "2") (pinfunction "2_2") (pintype "passive"))
      (node (ref "R4") (pin "2") (pinfunction "2_2") (pintype "passive"))
    )
    (net (code "81") (name "Net-(4-Pad3)") (class "Default")
      (node (ref "4") (pin "3") (pinfunction "3_3") (pintype "passive"))
      (node (ref "5") (pin "3") (pinfunction "3_3") (pintype "passive"))
      (node (ref "R8") (pin "2") (pinfunction "2_2") (pintype "passive"))
    )
    (net (code "82") (name "Net-(4-Pad4)") (class "Default")
      (node (ref "4") (pin "4") (pinfunction "4_4") (pintype "passive"))
      (node (ref "5") (pin "4") (pinfunction "4_4") (pintype "passive"))
      (node (ref "R3") (pin "2") (pinfunction "2_2") (pintype "passive"))
    )
    (net (code "83") (name "Net-(4-Pad5)") (class "Default")
      (node (ref "4") (pin "5") (pinfunction "5_5") (pintype "passive"))
      (node (ref "5") (pin "5") (pinfunction "5_5") (pintype "passive"))
      (node (ref "R7") (pin "2") (pinfunction "2_2") (pintype "passive"))
    )
    (net (code "84") (name "Net-(4-Pad7)") (class "Default")
      (node (ref "4") (pin "7") (pinfunction "7_7") (pintype "passive"))
      (node (ref "5") (pin "7") (pinfunction "7_7") (pintype "passive"))
      (node (ref "R2") (pin "2") (pinfunction "2_2") (pintype "passive"))
    )
    (net (code "85") (name "Net-(4-Pad10)") (class "Default")
      (node (ref "4") (pin "10") (pinfunction "10_10") (pintype "passive"))
      (node (ref "5") (pin "10") (pinfunction "10_10") (pintype "passive"))
      (node (ref "R6") (pin "2") (pinfunction "2_2") (pintype "passive"))
    )
    (net (code "86") (name "Net-(4-Pad11)") (class "Default")
      (node (ref "4") (pin "11") (pinfunction "11_11") (pintype "passive"))
      (node (ref "5") (pin "11") (pinfunction "11_11") (pintype "passive"))
      (node (ref "R1") (pin "2") (pinfunction "2_2") (pintype "passive"))
    )
    (net (code "87") (name "Net-(4-d1)") (class "Default")
      (node (ref "4") (pin "12") (pinfunction "d1_12") (pintype "passive"))
      (node (ref "9") (pin "c") (pinfunction "3_c") (pintype "passive"))
    )
    (net (code "88") (name "Net-(9-2)") (class "Default")
      (node (ref "9") (pin "b") (pinfunction "2_b") (pintype "passive"))
      (node (ref "R9") (pin "2") (pinfunction "2_2") (pintype "passive"))
    )
    (net (code "89") (name "Net-(10-2)") (class "Default")
      (node (ref "10") (pin "b") (pinfunction "2_b") (pintype "passive"))
      (node (ref "R10") (pin "2") (pinfunction "2_2") (pintype "passive"))
    )
    (net (code "90") (name "Net-(10-3)") (class "Default")
      (node (ref "10") (pin "c") (pinfunction "3_c") (pintype "passive"))
      (node (ref "4") (pin "9") (pinfunction "5_9") (pintype "passive"))
    )
    (net (code "91") (name "Net-(11-2)") (class "Default")
      (node (ref "11") (pin "b") (pinfunction "2_b") (pintype "passive"))
      (node (ref "R16") (pin "2") (pinfunction "2_2") (pintype "passive"))
    )
    (net (code "92") (name "Net-(11-3)") (class "Default")
      (node (ref "11") (pin "c") (pinfunction "3_c") (pintype "passive"))
      (node (ref "4") (pin "8") (pinfunction "6_8") (pintype "passive"))
    )
    (net (code "93") (name "Net-(12-2)") (class "Default")
      (node (ref "12") (pin "b") (pinfunction "2_b") (pintype "passive"))
      (node (ref "R11") (pin "2") (pinfunction "2_2") (pintype "passive"))
    )
    (net (code "94") (name "Net-(12-3)") (class "Default")
      (node (ref "12") (pin "c") (pinfunction "3_c") (pintype "passive"))
      (node (ref "4") (pin "6") (pinfunction "6_6") (pintype "passive"))
    )
    (net (code "95") (name "Net-(13-2)") (class "Default")
      (node (ref "13") (pin "b") (pinfunction "2_b") (pintype "passive"))
      (node (ref "R12") (pin "2") (pinfunction "2_2") (pintype "passive"))
    )
    (net (code "96") (name "Net-(13-3)") (class "Default")
      (node (ref "13") (pin "c") (pinfunction "3_c") (pintype "passive"))
      (node (ref "5") (pin "12") (pinfunction "d1_12") (pintype "passive"))
    )
    (net (code "97") (name "Net-(14-2)") (class "Default")
      (node (ref "14") (pin "b") (pinfunction "2_b") (pintype "passive"))
      (node (ref "R13") (pin "2") (pinfunction "2_2") (pintype "passive"))
    )
    (net (code "98") (name "Net-(14-3)") (class "Default")
      (node (ref "14") (pin "c") (pinfunction "3_c") (pintype "passive"))
      (node (ref "5") (pin "9") (pinfunction "5_9") (pintype "passive"))
    )
    (net (code "99") (name "Net-(15-2)") (class "Default")
      (node (ref "15") (pin "b") (pinfunction "2_b") (pintype "passive"))
      (node (ref "R14") (pin "2") (pinfunction "2_2") (pintype "passive"))
    )
    (net (code "100") (name "Net-(15-3)") (class "Default")
      (node (ref "15") (pin "c") (pinfunction "3_c") (pintype "passive"))
      (node (ref "5") (pin "8") (pinfunction "6_8") (pintype "passive"))
    )
    (net (code "101") (name "Net-(16-2)") (class "Default")
      (node (ref "16") (pin "b") (pinfunction "2_b") (pintype "passive"))
      (node (ref "R15") (pin "2") (pinfunction "2_2") (pintype "passive"))
    )
    (net (code "102") (name "Net-(16-3)") (class "Default")
      (node (ref "16") (pin "c") (pinfunction "3_c") (pintype "passive"))
      (node (ref "5") (pin "6") (pinfunction "6_6") (pintype "passive"))
    )
    (net (code "103") (name "Net-(DS1-K)") (class "Default")
      (node (ref "DS1") (pin "2") (pinfunction "K_2") (pintype "passive"))
      (node (ref "R18") (pin "2") (pinfunction "2_2") (pintype "passive"))
    )
    (net (code "104") (name "Net-(LED1-K)") (class "Default")
      (node (ref "LED1") (pin "2") (pinfunction "K_2") (pintype "passive"))
      (node (ref "R19") (pin "2") (pinfunction "2_2") (pintype "passive"))
    )
    (net (code "105") (name "Net-(LED2-K)") (class "Default")
      (node (ref "LED2") (pin "2") (pinfunction "K_2") (pintype "passive"))
      (node (ref "R20") (pin "2") (pinfunction "2_2") (pintype "passive"))
    )
    (net (code "106") (name "Net-(LED3-K)") (class "Default")
      (node (ref "LED3") (pin "2") (pinfunction "K_2") (pintype "passive"))
      (node (ref "R21") (pin "2") (pinfunction "2_2") (pintype "passive"))
    )
    (net (code "107") (name "Net-(LED4-K)") (class "Default")
      (node (ref "LED4") (pin "2") (pinfunction "K_2") (pintype "passive"))
      (node (ref "R22") (pin "2") (pinfunction "2_2") (pintype "passive"))
    )
    (net (code "108") (name "Net-(LED5-K)") (class "Default")
      (node (ref "LED5") (pin "2") (pinfunction "K_2") (pintype "passive"))
      (node (ref "R23") (pin "2") (pinfunction "2_2") (pintype "passive"))
    )
    (net (code "109") (name "Net-(LED6-K)") (class "Default")
      (node (ref "LED6") (pin "2") (pinfunction "K_2") (pintype "passive"))
      (node (ref "R24") (pin "2") (pinfunction "2_2") (pintype "passive"))
    )
    (net (code "110") (name "Net-(LED7-K)") (class "Default")
      (node (ref "LED7") (pin "2") (pinfunction "K_2") (pintype "passive"))
      (node (ref "R25") (pin "2") (pinfunction "2_2") (pintype "passive"))
    )
    (net (code "111") (name "Net-(LED8-K)") (class "Default")
      (node (ref "LED8") (pin "2") (pinfunction "K_2") (pintype "passive"))
      (node (ref "R26") (pin "2") (pinfunction "2_2") (pintype "passive"))
    )
    (net (code "112") (name "Net-(P1-Pad1)") (class "Default")
      (node (ref "P1") (pin "1") (pinfunction "1_1") (pintype "passive"))
      (node (ref "R8") (pin "1") (pinfunction "1_1") (pintype "passive"))
    )
    (net (code "113") (name "Net-(P1-Pad2)") (class "Default")
      (node (ref "P1") (pin "2") (pinfunction "2_2") (pintype "passive"))
      (node (ref "R7") (pin "1") (pinfunction "1_1") (pintype "passive"))
    )
    (net (code "114") (name "Net-(P1-Pad3)") (class "Default")
      (node (ref "P1") (pin "3") (pinfunction "3_3") (pintype "passive"))
      (node (ref "R6") (pin "1") (pinfunction "1_1") (pintype "passive"))
    )
    (net (code "115") (name "Net-(P1-Pad4)") (class "Default")
      (node (ref "P1") (pin "4") (pinfunction "4_4") (pintype "passive"))
      (node (ref "R5") (pin "1") (pinfunction "1_1") (pintype "passive"))
    )
    (net (code "116") (name "Net-(P1-Pad5)") (class "Default")
      (node (ref "P1") (pin "5") (pinfunction "5_5") (pintype "passive"))
      (node (ref "R4") (pin "1") (pinfunction "1_1") (pintype "passive"))
    )
    (net (code "117") (name "Net-(P1-Pad6)") (class "Default")
      (node (ref "P1") (pin "6") (pinfunction "6_6") (pintype "passive"))
      (node (ref "R3") (pin "1") (pinfunction "1_1") (pintype "passive"))
    )
    (net (code "118") (name "Net-(P1-Pad7)") (class "Default")
      (node (ref "P1") (pin "7") (pinfunction "7_7") (pintype "passive"))
      (node (ref "R2") (pin "1") (pinfunction "1_1") (pintype "passive"))
    )
    (net (code "119") (name "Net-(P1-Pad8)") (class "Default")
      (node (ref "P1") (pin "8") (pinfunction "8_8") (pintype "passive"))
      (node (ref "R1") (pin "1") (pinfunction "1_1") (pintype "passive"))
    )
    (net (code "120") (name "Net-(S1-COMMON1)") (class "Default")
      (node (ref "PROWER1") (pin "1") (pinfunction "1_1") (pintype "passive"))
      (node (ref "S1") (pin "1") (pinfunction "COMMON1_1") (pintype "passive"))
      (node (ref "USB1") (pin "1") (pinfunction "1_1") (pintype "passive"))
    )
    (net (code "121") (name "Net-(S1-COMMON2)") (class "Default")
      (node (ref "PROWER1") (pin "2") (pinfunction "2_2") (pintype "passive"))
      (node (ref "S1") (pin "5") (pinfunction "COMMON2_5") (pintype "passive"))
      (node (ref "USB1") (pin "4") (pinfunction "4_4") (pintype "passive"))
    )
    (net (code "122") (name "Net-(U1-C1+)") (class "Default")
      (node (ref "C10") (pin "1") (pinfunction "1_1") (pintype "passive"))
      (node (ref "U1") (pin "1") (pinfunction "C1+_1") (pintype "passive"))
    )
    (net (code "123") (name "Net-(U1-C1-)") (class "Default")
      (node (ref "C10") (pin "2") (pinfunction "2_2") (pintype "passive"))
      (node (ref "U1") (pin "3") (pinfunction "C1-_3") (pintype "passive"))
    )
    (net (code "124") (name "Net-(U1-C2+)") (class "Default")
      (node (ref "C12") (pin "1") (pinfunction "1_1") (pintype "passive"))
      (node (ref "U1") (pin "4") (pinfunction "C2+_4") (pintype "passive"))
    )
    (net (code "125") (name "Net-(U1-C2-)") (class "Default")
      (node (ref "C12") (pin "2") (pinfunction "2_2") (pintype "passive"))
      (node (ref "U1") (pin "5") (pinfunction "C2-_5") (pintype "passive"))
    )
    (net (code "126") (name "Net-(U1-R1IN)") (class "Default")
      (node (ref "COM2") (pin "3") (pinfunction "3_3") (pintype "passive"))
      (node (ref "U1") (pin "13") (pinfunction "R1IN_13") (pintype "input"))
    )
    (net (code "127") (name "Net-(U1-R2IN)") (class "Default")
      (node (ref "COM1") (pin "3") (pinfunction "3_3") (pintype "passive"))
      (node (ref "U1") (pin "8") (pinfunction "R2IN_8") (pintype "input"))
    )
    (net (code "128") (name "Net-(U1-T1OUT)") (class "Default")
      (node (ref "COM2") (pin "2") (pinfunction "2_2") (pintype "passive"))
      (node (ref "U1") (pin "14") (pinfunction "T1OUT_14") (pintype "output"))
    )
    (net (code "129") (name "Net-(U1-T2OUT)") (class "Default")
      (node (ref "COM1") (pin "2") (pinfunction "2_2") (pintype "passive"))
      (node (ref "U1") (pin "7") (pinfunction "T2OUT_7") (pintype "output"))
    )
    (net (code "130") (name "Net-(U1-VDD)") (class "Default")
      (node (ref "C11") (pin "1") (pinfunction "1_1") (pintype "passive"))
      (node (ref "U1") (pin "2") (pinfunction "VDD_2") (pintype "power_in"))
    )
    (net (code "131") (name "Net-(U1-VEE)") (class "Default")
      (node (ref "C14") (pin "2") (pinfunction "2_2") (pintype "passive"))
      (node (ref "U1") (pin "6") (pinfunction "VEE_6") (pintype "power_in"))
    )
    (net (code "132") (name "VCC") (class "Default")
      (node (ref "10") (pin "e") (pinfunction "1_e") (pintype "passive"))
      (node (ref "11") (pin "e") (pinfunction "1_e") (pintype "passive"))
      (node (ref "12") (pin "e") (pinfunction "1_e") (pintype "passive"))
      (node (ref "13") (pin "e") (pinfunction "1_e") (pintype "passive"))
      (node (ref "14") (pin "e") (pinfunction "1_e") (pintype "passive"))
      (node (ref "15") (pin "e") (pinfunction "1_e") (pintype "passive"))
      (node (ref "16") (pin "e") (pinfunction "1_e") (pintype "passive"))
      (node (ref "9") (pin "e") (pinfunction "1_e") (pintype "passive"))
      (node (ref "C6") (pin "1") (pinfunction "1_1") (pintype "passive"))
      (node (ref "C7") (pin "2") (pinfunction "2_2") (pintype "passive"))
      (node (ref "C8") (pin "1") (pinfunction "1_1") (pintype "passive"))
      (node (ref "C9") (pin "1") (pinfunction "1_1") (pintype "passive"))
      (node (ref "DS1") (pin "1") (pinfunction "A_1") (pintype "passive"))
      (node (ref "DownLoad1") (pin "2") (pinfunction "2_2") (pintype "passive"))
      (node (ref "LED1") (pin "1") (pinfunction "A_1") (pintype "passive"))
      (node (ref "LED2") (pin "1") (pinfunction "A_1") (pintype "passive"))
      (node (ref "LED3") (pin "1") (pinfunction "A_1") (pintype "passive"))
      (node (ref "LED4") (pin "1") (pinfunction "A_1") (pintype "passive"))
      (node (ref "LED5") (pin "1") (pinfunction "A_1") (pintype "passive"))
      (node (ref "LED6") (pin "1") (pinfunction "A_1") (pintype "passive"))
      (node (ref "LED7") (pin "1") (pinfunction "A_1") (pintype "passive"))
      (node (ref "LED8") (pin "1") (pinfunction "A_1") (pintype "passive"))
      (node (ref "MSP1") (pin "1") (pinfunction "DVCC_1") (pintype "passive"))
      (node (ref "MSP1") (pin "64") (pinfunction "AVCC_64") (pintype "passive"))
      (node (ref "P4") (pin "1") (pinfunction "1_1") (pintype "passive"))
      (node (ref "P7") (pin "16") (pinfunction "16_16") (pintype "passive"))
      (node (ref "P9") (pin "4") (pinfunction "4_4") (pintype "passive"))
      (node (ref "P9") (pin "5") (pinfunction "5_5") (pintype "passive"))
      (node (ref "R17") (pin "1") (pinfunction "1_1") (pintype "passive"))
      (node (ref "REG1") (pin "2") (pinfunction "OUT_2") (pintype "power_in"))
      (node (ref "REG1") (pin "4") (pinfunction "OUT_4") (pintype "power_in"))
      (node (ref "RP_1") (pin "1") (pinfunction "1_1") (pintype "passive"))
    )
    (net (code "133") (name "unconnected-(COM1-MH1-Pad10)") (class "Default")
      (node (ref "COM1") (pin "10") (pinfunction "MH1_10") (pintype "passive"))
    )
    (net (code "134") (name "unconnected-(COM1-MH2-Pad11)") (class "Default")
      (node (ref "COM1") (pin "11") (pinfunction "MH2_11") (pintype "passive"))
    )
    (net (code "135") (name "unconnected-(COM1-Pad1)") (class "Default")
      (node (ref "COM1") (pin "1") (pinfunction "1_1") (pintype "passive"))
    )
    (net (code "136") (name "unconnected-(COM1-Pad4)") (class "Default")
      (node (ref "COM1") (pin "4") (pinfunction "4_4") (pintype "passive"))
    )
    (net (code "137") (name "unconnected-(COM1-Pad5)") (class "Default")
      (node (ref "COM1") (pin "5") (pinfunction "5_5") (pintype "passive"))
    )
    (net (code "138") (name "unconnected-(COM1-Pad6)") (class "Default")
      (node (ref "COM1") (pin "6") (pinfunction "6_6") (pintype "passive"))
    )
    (net (code "139") (name "unconnected-(COM1-Pad7)") (class "Default")
      (node (ref "COM1") (pin "7") (pinfunction "7_7") (pintype "passive"))
    )
    (net (code "140") (name "unconnected-(COM1-Pad8)") (class "Default")
      (node (ref "COM1") (pin "8") (pinfunction "8_8") (pintype "passive"))
    )
    (net (code "141") (name "unconnected-(COM1-Pad9)") (class "Default")
      (node (ref "COM1") (pin "9") (pinfunction "9_9") (pintype "passive"))
    )
    (net (code "142") (name "unconnected-(COM2-MH1-Pad10)") (class "Default")
      (node (ref "COM2") (pin "10") (pinfunction "MH1_10") (pintype "passive"))
    )
    (net (code "143") (name "unconnected-(COM2-MH2-Pad11)") (class "Default")
      (node (ref "COM2") (pin "11") (pinfunction "MH2_11") (pintype "passive"))
    )
    (net (code "144") (name "unconnected-(COM2-Pad1)") (class "Default")
      (node (ref "COM2") (pin "1") (pinfunction "1_1") (pintype "passive"))
    )
    (net (code "145") (name "unconnected-(COM2-Pad4)") (class "Default")
      (node (ref "COM2") (pin "4") (pinfunction "4_4") (pintype "passive"))
    )
    (net (code "146") (name "unconnected-(COM2-Pad5)") (class "Default")
      (node (ref "COM2") (pin "5") (pinfunction "5_5") (pintype "passive"))
    )
    (net (code "147") (name "unconnected-(COM2-Pad6)") (class "Default")
      (node (ref "COM2") (pin "6") (pinfunction "6_6") (pintype "passive"))
    )
    (net (code "148") (name "unconnected-(COM2-Pad7)") (class "Default")
      (node (ref "COM2") (pin "7") (pinfunction "7_7") (pintype "passive"))
    )
    (net (code "149") (name "unconnected-(COM2-Pad8)") (class "Default")
      (node (ref "COM2") (pin "8") (pinfunction "8_8") (pintype "passive"))
    )
    (net (code "150") (name "unconnected-(COM2-Pad9)") (class "Default")
      (node (ref "COM2") (pin "9") (pinfunction "9_9") (pintype "passive"))
    )
    (net (code "151") (name "unconnected-(DownLoad1-Pad4)") (class "Default")
      (node (ref "DownLoad1") (pin "4") (pinfunction "4_4") (pintype "passive"))
    )
    (net (code "152") (name "unconnected-(DownLoad1-Pad6)") (class "Default")
      (node (ref "DownLoad1") (pin "6") (pinfunction "6_6") (pintype "passive"))
    )
    (net (code "153") (name "unconnected-(DownLoad1-Pad8)") (class "Default")
      (node (ref "DownLoad1") (pin "8") (pinfunction "8_8") (pintype "passive"))
    )
    (net (code "154") (name "unconnected-(DownLoad1-Pad10)") (class "Default")
      (node (ref "DownLoad1") (pin "10") (pinfunction "10_10") (pintype "passive"))
    )
    (net (code "155") (name "unconnected-(DownLoad1-Pad12)") (class "Default")
      (node (ref "DownLoad1") (pin "12") (pinfunction "12_12") (pintype "passive"))
    )
    (net (code "156") (name "unconnected-(DownLoad1-Pad13)") (class "Default")
      (node (ref "DownLoad1") (pin "13") (pinfunction "13_13") (pintype "passive"))
    )
    (net (code "157") (name "unconnected-(DownLoad1-Pad14)") (class "Default")
      (node (ref "DownLoad1") (pin "14") (pinfunction "14_14") (pintype "passive"))
    )
    (net (code "158") (name "unconnected-(P3-Pad1)") (class "Default")
      (node (ref "P3") (pin "1") (pinfunction "1_1") (pintype "passive"))
    )
    (net (code "159") (name "unconnected-(P3-Pad2)") (class "Default")
      (node (ref "P3") (pin "2") (pinfunction "2_2") (pintype "passive"))
    )
    (net (code "160") (name "unconnected-(P3-Pad3)") (class "Default")
      (node (ref "P3") (pin "3") (pinfunction "3_3") (pintype "passive"))
    )
    (net (code "161") (name "unconnected-(P3-Pad4)") (class "Default")
      (node (ref "P3") (pin "4") (pinfunction "4_4") (pintype "passive"))
    )
    (net (code "162") (name "unconnected-(P3-Pad5)") (class "Default")
      (node (ref "P3") (pin "5") (pinfunction "5_5") (pintype "passive"))
    )
    (net (code "163") (name "unconnected-(P3-Pad6)") (class "Default")
      (node (ref "P3") (pin "6") (pinfunction "6_6") (pintype "passive"))
    )
    (net (code "164") (name "unconnected-(P3-Pad7)") (class "Default")
      (node (ref "P3") (pin "7") (pinfunction "7_7") (pintype "passive"))
    )
    (net (code "165") (name "unconnected-(P3-Pad8)") (class "Default")
      (node (ref "P3") (pin "8") (pinfunction "8_8") (pintype "passive"))
    )
    (net (code "166") (name "unconnected-(R9-Pad1)") (class "Default")
      (node (ref "R9") (pin "1") (pinfunction "1_1") (pintype "passive"))
    )
    (net (code "167") (name "unconnected-(R10-Pad1)") (class "Default")
      (node (ref "R10") (pin "1") (pinfunction "1_1") (pintype "passive"))
    )
    (net (code "168") (name "unconnected-(R11-Pad1)") (class "Default")
      (node (ref "R11") (pin "1") (pinfunction "1_1") (pintype "passive"))
    )
    (net (code "169") (name "unconnected-(R12-Pad1)") (class "Default")
      (node (ref "R12") (pin "1") (pinfunction "1_1") (pintype "passive"))
    )
    (net (code "170") (name "unconnected-(R13-Pad1)") (class "Default")
      (node (ref "R13") (pin "1") (pinfunction "1_1") (pintype "passive"))
    )
    (net (code "171") (name "unconnected-(R14-Pad1)") (class "Default")
      (node (ref "R14") (pin "1") (pinfunction "1_1") (pintype "passive"))
    )
    (net (code "172") (name "unconnected-(R15-Pad1)") (class "Default")
      (node (ref "R15") (pin "1") (pinfunction "1_1") (pintype "passive"))
    )
    (net (code "173") (name "unconnected-(R16-Pad1)") (class "Default")
      (node (ref "R16") (pin "1") (pinfunction "1_1") (pintype "passive"))
    )
    (net (code "174") (name "unconnected-(S1-NC1-Pad2)") (class "Default")
      (node (ref "S1") (pin "2") (pinfunction "NC1_2") (pintype "passive"))
    )
    (net (code "175") (name "unconnected-(S1-NC2-Pad4)") (class "Default")
      (node (ref "S1") (pin "4") (pinfunction "NC2_4") (pintype "passive"))
    )
    (net (code "176") (name "unconnected-(USB1-Pad2)") (class "Default")
      (node (ref "USB1") (pin "2") (pinfunction "2_2") (pintype "passive"))
    )
    (net (code "177") (name "unconnected-(USB1-Pad3)") (class "Default")
      (node (ref "USB1") (pin "3") (pinfunction "3_3") (pintype "passive"))
    )
  )
)
